# Buttons.net
KiCad netlist of a schematic drawn in EAGLE
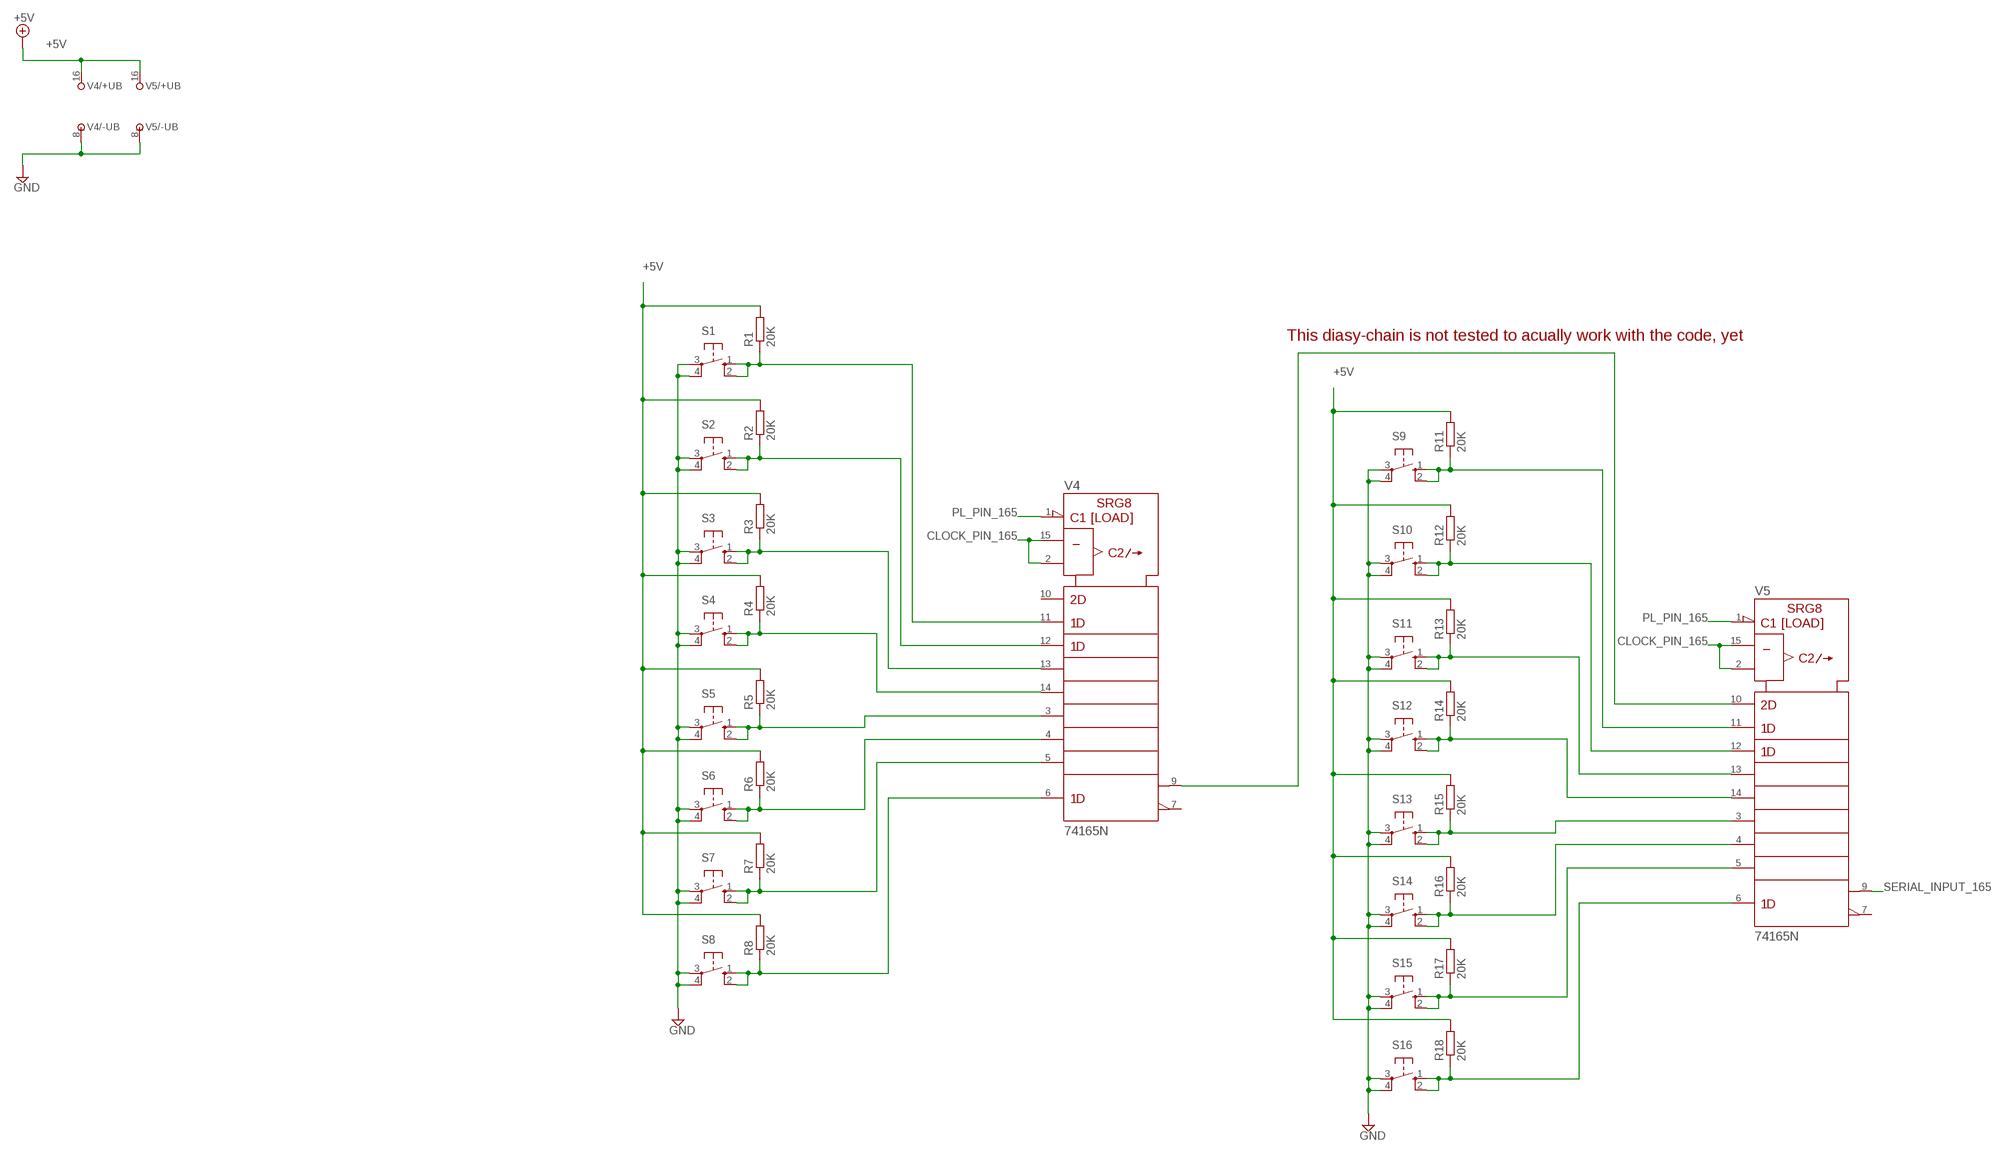
[diagram p0: schematic, sheet 1]

(export (version "E")
  (design (tool "Eeschema 10.0.6"))
  (components
    (comp (ref "R1")
      (value "20K")
      (footprint "eagle-import:0204_7")
      (libsource (lib "eagle-import") (part "R-EU_0204/7"))
    )
    (comp (ref "R2")
      (value "20K")
      (footprint "eagle-import:0204_7")
      (libsource (lib "eagle-import") (part "R-EU_0204/7"))
    )
    (comp (ref "R3")
      (value "20K")
      (footprint "eagle-import:0204_7")
      (libsource (lib "eagle-import") (part "R-EU_0204/7"))
    )
    (comp (ref "R4")
      (value "20K")
      (footprint "eagle-import:0204_7")
      (libsource (lib "eagle-import") (part "R-EU_0204/7"))
    )
    (comp (ref "R5")
      (value "20K")
      (footprint "eagle-import:0204_7")
      (libsource (lib "eagle-import") (part "R-EU_0204/7"))
    )
    (comp (ref "R6")
      (value "20K")
      (footprint "eagle-import:0204_7")
      (libsource (lib "eagle-import") (part "R-EU_0204/7"))
    )
    (comp (ref "R7")
      (value "20K")
      (footprint "eagle-import:0204_7")
      (libsource (lib "eagle-import") (part "R-EU_0204/7"))
    )
    (comp (ref "R8")
      (value "20K")
      (footprint "eagle-import:0204_7")
      (libsource (lib "eagle-import") (part "R-EU_0204/7"))
    )
    (comp (ref "R11")
      (value "20K")
      (footprint "eagle-import:0204_7")
      (libsource (lib "eagle-import") (part "R-EU_0204/7"))
    )
    (comp (ref "R12")
      (value "20K")
      (footprint "eagle-import:0204_7")
      (libsource (lib "eagle-import") (part "R-EU_0204/7"))
    )
    (comp (ref "R13")
      (value "20K")
      (footprint "eagle-import:0204_7")
      (libsource (lib "eagle-import") (part "R-EU_0204/7"))
    )
    (comp (ref "R14")
      (value "20K")
      (footprint "eagle-import:0204_7")
      (libsource (lib "eagle-import") (part "R-EU_0204/7"))
    )
    (comp (ref "R15")
      (value "20K")
      (footprint "eagle-import:0204_7")
      (libsource (lib "eagle-import") (part "R-EU_0204/7"))
    )
    (comp (ref "R16")
      (value "20K")
      (footprint "eagle-import:0204_7")
      (libsource (lib "eagle-import") (part "R-EU_0204/7"))
    )
    (comp (ref "R17")
      (value "20K")
      (footprint "eagle-import:0204_7")
      (libsource (lib "eagle-import") (part "R-EU_0204/7"))
    )
    (comp (ref "R18")
      (value "20K")
      (footprint "eagle-import:0204_7")
      (libsource (lib "eagle-import") (part "R-EU_0204/7"))
    )
    (comp (ref "S1")
      (value "40-XX")
      (footprint "eagle-import:B3F-40XX")
      (fields (field (name "MF") "OMRON COMPONENTS USA") (field (name "MPN") "B3F-4000"))
      (libsource (lib "eagle-import") (part "40-XX"))
    )
    (comp (ref "S2")
      (value "40-XX")
      (footprint "eagle-import:B3F-40XX")
      (fields (field (name "MF") "OMRON COMPONENTS USA") (field (name "MPN") "B3F-4000"))
      (libsource (lib "eagle-import") (part "40-XX"))
    )
    (comp (ref "S3")
      (value "40-XX")
      (footprint "eagle-import:B3F-40XX")
      (fields (field (name "MF") "OMRON COMPONENTS USA") (field (name "MPN") "B3F-4000"))
      (libsource (lib "eagle-import") (part "40-XX"))
    )
    (comp (ref "S4")
      (value "40-XX")
      (footprint "eagle-import:B3F-40XX")
      (fields (field (name "MF") "OMRON COMPONENTS USA") (field (name "MPN") "B3F-4000"))
      (libsource (lib "eagle-import") (part "40-XX"))
    )
    (comp (ref "S5")
      (value "40-XX")
      (footprint "eagle-import:B3F-40XX")
      (fields (field (name "MF") "OMRON COMPONENTS USA") (field (name "MPN") "B3F-4000"))
      (libsource (lib "eagle-import") (part "40-XX"))
    )
    (comp (ref "S6")
      (value "40-XX")
      (footprint "eagle-import:B3F-40XX")
      (fields (field (name "MF") "OMRON COMPONENTS USA") (field (name "MPN") "B3F-4000"))
      (libsource (lib "eagle-import") (part "40-XX"))
    )
    (comp (ref "S7")
      (value "40-XX")
      (footprint "eagle-import:B3F-40XX")
      (fields (field (name "MF") "OMRON COMPONENTS USA") (field (name "MPN") "B3F-4000"))
      (libsource (lib "eagle-import") (part "40-XX"))
    )
    (comp (ref "S8")
      (value "40-XX")
      (footprint "eagle-import:B3F-40XX")
      (fields (field (name "MF") "OMRON COMPONENTS USA") (field (name "MPN") "B3F-4000"))
      (libsource (lib "eagle-import") (part "40-XX"))
    )
    (comp (ref "S9")
      (value "40-XX")
      (footprint "eagle-import:B3F-40XX")
      (fields (field (name "MF") "OMRON COMPONENTS USA") (field (name "MPN") "B3F-4000"))
      (libsource (lib "eagle-import") (part "40-XX"))
    )
    (comp (ref "S10")
      (value "40-XX")
      (footprint "eagle-import:B3F-40XX")
      (fields (field (name "MF") "OMRON COMPONENTS USA") (field (name "MPN") "B3F-4000"))
      (libsource (lib "eagle-import") (part "40-XX"))
    )
    (comp (ref "S11")
      (value "40-XX")
      (footprint "eagle-import:B3F-40XX")
      (fields (field (name "MF") "OMRON COMPONENTS USA") (field (name "MPN") "B3F-4000"))
      (libsource (lib "eagle-import") (part "40-XX"))
    )
    (comp (ref "S12")
      (value "40-XX")
      (footprint "eagle-import:B3F-40XX")
      (fields (field (name "MF") "OMRON COMPONENTS USA") (field (name "MPN") "B3F-4000"))
      (libsource (lib "eagle-import") (part "40-XX"))
    )
    (comp (ref "S13")
      (value "40-XX")
      (footprint "eagle-import:B3F-40XX")
      (fields (field (name "MF") "OMRON COMPONENTS USA") (field (name "MPN") "B3F-4000"))
      (libsource (lib "eagle-import") (part "40-XX"))
    )
    (comp (ref "S14")
      (value "40-XX")
      (footprint "eagle-import:B3F-40XX")
      (fields (field (name "MF") "OMRON COMPONENTS USA") (field (name "MPN") "B3F-4000"))
      (libsource (lib "eagle-import") (part "40-XX"))
    )
    (comp (ref "S15")
      (value "40-XX")
      (footprint "eagle-import:B3F-40XX")
      (fields (field (name "MF") "OMRON COMPONENTS USA") (field (name "MPN") "B3F-4000"))
      (libsource (lib "eagle-import") (part "40-XX"))
    )
    (comp (ref "S16")
      (value "40-XX")
      (footprint "eagle-import:B3F-40XX")
      (fields (field (name "MF") "OMRON COMPONENTS USA") (field (name "MPN") "B3F-4000"))
      (libsource (lib "eagle-import") (part "40-XX"))
    )
    (comp (ref "V4")
      (value "74165N")
      (footprint "eagle-import:DIL16")
      (libsource (lib "eagle-import") (part "74165N"))
    )
    (comp (ref "V5")
      (value "74165N")
      (footprint "eagle-import:DIL16")
      (libsource (lib "eagle-import") (part "74165N"))
    )
  )
  (nets
    (net (code "1") (name "+5V") (class "Default")
      (node (ref "R1") (pin "2") (pinfunction "2_2") (pintype "passive"))
      (node (ref "R11") (pin "2") (pinfunction "2_2") (pintype "passive"))
      (node (ref "R12") (pin "2") (pinfunction "2_2") (pintype "passive"))
      (node (ref "R13") (pin "2") (pinfunction "2_2") (pintype "passive"))
      (node (ref "R14") (pin "2") (pinfunction "2_2") (pintype "passive"))
      (node (ref "R15") (pin "2") (pinfunction "2_2") (pintype "passive"))
      (node (ref "R16") (pin "2") (pinfunction "2_2") (pintype "passive"))
      (node (ref "R17") (pin "2") (pinfunction "2_2") (pintype "passive"))
      (node (ref "R18") (pin "2") (pinfunction "2_2") (pintype "passive"))
      (node (ref "R2") (pin "2") (pinfunction "2_2") (pintype "passive"))
      (node (ref "R3") (pin "2") (pinfunction "2_2") (pintype "passive"))
      (node (ref "R4") (pin "2") (pinfunction "2_2") (pintype "passive"))
      (node (ref "R5") (pin "2") (pinfunction "2_2") (pintype "passive"))
      (node (ref "R6") (pin "2") (pinfunction "2_2") (pintype "passive"))
      (node (ref "R7") (pin "2") (pinfunction "2_2") (pintype "passive"))
      (node (ref "R8") (pin "2") (pinfunction "2_2") (pintype "passive"))
      (node (ref "V4") (pin "16") (pinfunction "+UB_16") (pintype "power_in"))
      (node (ref "V5") (pin "16") (pinfunction "+UB_16") (pintype "power_in"))
    )
    (net (code "2") (name "/CLOCK_PIN_165") (class "Default")
      (node (ref "V4") (pin "15") (pinfunction "CLK_INH_15") (pintype "input"))
      (node (ref "V4") (pin "2") (pinfunction "CLK_2") (pintype "input"))
      (node (ref "V5") (pin "15") (pinfunction "CLK_INH_15") (pintype "input"))
      (node (ref "V5") (pin "2") (pinfunction "CLK_2") (pintype "input"))
    )
    (net (code "3") (name "/PL_PIN_165") (class "Default")
      (node (ref "V4") (pin "1") (pinfunction "SH/~{LD}_1") (pintype "input"))
      (node (ref "V5") (pin "1") (pinfunction "SH/~{LD}_1") (pintype "input"))
    )
    (net (code "4") (name "/SERIAL_INPUT_165") (class "Default")
      (node (ref "V5") (pin "9") (pinfunction "QH_9") (pintype "output"))
    )
    (net (code "5") (name "GND") (class "Default")
      (node (ref "S1") (pin "3") (pinfunction "P_3") (pintype "passive"))
      (node (ref "S1") (pin "4") (pinfunction "P1_4") (pintype "passive"))
      (node (ref "S10") (pin "3") (pinfunction "P_3") (pintype "passive"))
      (node (ref "S10") (pin "4") (pinfunction "P1_4") (pintype "passive"))
      (node (ref "S11") (pin "3") (pinfunction "P_3") (pintype "passive"))
      (node (ref "S11") (pin "4") (pinfunction "P1_4") (pintype "passive"))
      (node (ref "S12") (pin "3") (pinfunction "P_3") (pintype "passive"))
      (node (ref "S12") (pin "4") (pinfunction "P1_4") (pintype "passive"))
      (node (ref "S13") (pin "3") (pinfunction "P_3") (pintype "passive"))
      (node (ref "S13") (pin "4") (pinfunction "P1_4") (pintype "passive"))
      (node (ref "S14") (pin "3") (pinfunction "P_3") (pintype "passive"))
      (node (ref "S14") (pin "4") (pinfunction "P1_4") (pintype "passive"))
      (node (ref "S15") (pin "3") (pinfunction "P_3") (pintype "passive"))
      (node (ref "S15") (pin "4") (pinfunction "P1_4") (pintype "passive"))
      (node (ref "S16") (pin "3") (pinfunction "P_3") (pintype "passive"))
      (node (ref "S16") (pin "4") (pinfunction "P1_4") (pintype "passive"))
      (node (ref "S2") (pin "3") (pinfunction "P_3") (pintype "passive"))
      (node (ref "S2") (pin "4") (pinfunction "P1_4") (pintype "passive"))
      (node (ref "S3") (pin "3") (pinfunction "P_3") (pintype "passive"))
      (node (ref "S3") (pin "4") (pinfunction "P1_4") (pintype "passive"))
      (node (ref "S4") (pin "3") (pinfunction "P_3") (pintype "passive"))
      (node (ref "S4") (pin "4") (pinfunction "P1_4") (pintype "passive"))
      (node (ref "S5") (pin "3") (pinfunction "P_3") (pintype "passive"))
      (node (ref "S5") (pin "4") (pinfunction "P1_4") (pintype "passive"))
      (node (ref "S6") (pin "3") (pinfunction "P_3") (pintype "passive"))
      (node (ref "S6") (pin "4") (pinfunction "P1_4") (pintype "passive"))
      (node (ref "S7") (pin "3") (pinfunction "P_3") (pintype "passive"))
      (node (ref "S7") (pin "4") (pinfunction "P1_4") (pintype "passive"))
      (node (ref "S8") (pin "3") (pinfunction "P_3") (pintype "passive"))
      (node (ref "S8") (pin "4") (pinfunction "P1_4") (pintype "passive"))
      (node (ref "S9") (pin "3") (pinfunction "P_3") (pintype "passive"))
      (node (ref "S9") (pin "4") (pinfunction "P1_4") (pintype "passive"))
      (node (ref "V4") (pin "8") (pinfunction "-UB_8") (pintype "power_in"))
      (node (ref "V5") (pin "8") (pinfunction "-UB_8") (pintype "power_in"))
    )
    (net (code "6") (name "Net-(S1-S)") (class "Default")
      (node (ref "R1") (pin "1") (pinfunction "1_1") (pintype "passive"))
      (node (ref "S1") (pin "1") (pinfunction "S_1") (pintype "passive"))
      (node (ref "S1") (pin "2") (pinfunction "S1_2") (pintype "passive"))
      (node (ref "V4") (pin "11") (pinfunction "A_11") (pintype "input"))
    )
    (net (code "7") (name "Net-(S2-S)") (class "Default")
      (node (ref "R2") (pin "1") (pinfunction "1_1") (pintype "passive"))
      (node (ref "S2") (pin "1") (pinfunction "S_1") (pintype "passive"))
      (node (ref "S2") (pin "2") (pinfunction "S1_2") (pintype "passive"))
      (node (ref "V4") (pin "12") (pinfunction "B_12") (pintype "input"))
    )
    (net (code "8") (name "Net-(S3-S)") (class "Default")
      (node (ref "R3") (pin "1") (pinfunction "1_1") (pintype "passive"))
      (node (ref "S3") (pin "1") (pinfunction "S_1") (pintype "passive"))
      (node (ref "S3") (pin "2") (pinfunction "S1_2") (pintype "passive"))
      (node (ref "V4") (pin "13") (pinfunction "C_13") (pintype "input"))
    )
    (net (code "9") (name "Net-(S4-S)") (class "Default")
      (node (ref "R4") (pin "1") (pinfunction "1_1") (pintype "passive"))
      (node (ref "S4") (pin "1") (pinfunction "S_1") (pintype "passive"))
      (node (ref "S4") (pin "2") (pinfunction "S1_2") (pintype "passive"))
      (node (ref "V4") (pin "14") (pinfunction "D_14") (pintype "input"))
    )
    (net (code "10") (name "Net-(S5-S)") (class "Default")
      (node (ref "R5") (pin "1") (pinfunction "1_1") (pintype "passive"))
      (node (ref "S5") (pin "1") (pinfunction "S_1") (pintype "passive"))
      (node (ref "S5") (pin "2") (pinfunction "S1_2") (pintype "passive"))
      (node (ref "V4") (pin "3") (pinfunction "E_3") (pintype "input"))
    )
    (net (code "11") (name "Net-(S6-S)") (class "Default")
      (node (ref "R6") (pin "1") (pinfunction "1_1") (pintype "passive"))
      (node (ref "S6") (pin "1") (pinfunction "S_1") (pintype "passive"))
      (node (ref "S6") (pin "2") (pinfunction "S1_2") (pintype "passive"))
      (node (ref "V4") (pin "4") (pinfunction "F_4") (pintype "input"))
    )
    (net (code "12") (name "Net-(S7-S)") (class "Default")
      (node (ref "R7") (pin "1") (pinfunction "1_1") (pintype "passive"))
      (node (ref "S7") (pin "1") (pinfunction "S_1") (pintype "passive"))
      (node (ref "S7") (pin "2") (pinfunction "S1_2") (pintype "passive"))
      (node (ref "V4") (pin "5") (pinfunction "G_5") (pintype "input"))
    )
    (net (code "13") (name "Net-(S8-S)") (class "Default")
      (node (ref "R8") (pin "1") (pinfunction "1_1") (pintype "passive"))
      (node (ref "S8") (pin "1") (pinfunction "S_1") (pintype "passive"))
      (node (ref "S8") (pin "2") (pinfunction "S1_2") (pintype "passive"))
      (node (ref "V4") (pin "6") (pinfunction "H_6") (pintype "input"))
    )
    (net (code "14") (name "Net-(S9-S)") (class "Default")
      (node (ref "R11") (pin "1") (pinfunction "1_1") (pintype "passive"))
      (node (ref "S9") (pin "1") (pinfunction "S_1") (pintype "passive"))
      (node (ref "S9") (pin "2") (pinfunction "S1_2") (pintype "passive"))
      (node (ref "V5") (pin "11") (pinfunction "A_11") (pintype "input"))
    )
    (net (code "15") (name "Net-(S10-S)") (class "Default")
      (node (ref "R12") (pin "1") (pinfunction "1_1") (pintype "passive"))
      (node (ref "S10") (pin "1") (pinfunction "S_1") (pintype "passive"))
      (node (ref "S10") (pin "2") (pinfunction "S1_2") (pintype "passive"))
      (node (ref "V5") (pin "12") (pinfunction "B_12") (pintype "input"))
    )
    (net (code "16") (name "Net-(S11-S)") (class "Default")
      (node (ref "R13") (pin "1") (pinfunction "1_1") (pintype "passive"))
      (node (ref "S11") (pin "1") (pinfunction "S_1") (pintype "passive"))
      (node (ref "S11") (pin "2") (pinfunction "S1_2") (pintype "passive"))
      (node (ref "V5") (pin "13") (pinfunction "C_13") (pintype "input"))
    )
    (net (code "17") (name "Net-(S12-S)") (class "Default")
      (node (ref "R14") (pin "1") (pinfunction "1_1") (pintype "passive"))
      (node (ref "S12") (pin "1") (pinfunction "S_1") (pintype "passive"))
      (node (ref "S12") (pin "2") (pinfunction "S1_2") (pintype "passive"))
      (node (ref "V5") (pin "14") (pinfunction "D_14") (pintype "input"))
    )
    (net (code "18") (name "Net-(S13-S)") (class "Default")
      (node (ref "R15") (pin "1") (pinfunction "1_1") (pintype "passive"))
      (node (ref "S13") (pin "1") (pinfunction "S_1") (pintype "passive"))
      (node (ref "S13") (pin "2") (pinfunction "S1_2") (pintype "passive"))
      (node (ref "V5") (pin "3") (pinfunction "E_3") (pintype "input"))
    )
    (net (code "19") (name "Net-(S14-S)") (class "Default")
      (node (ref "R16") (pin "1") (pinfunction "1_1") (pintype "passive"))
      (node (ref "S14") (pin "1") (pinfunction "S_1") (pintype "passive"))
      (node (ref "S14") (pin "2") (pinfunction "S1_2") (pintype "passive"))
      (node (ref "V5") (pin "4") (pinfunction "F_4") (pintype "input"))
    )
    (net (code "20") (name "Net-(S15-S)") (class "Default")
      (node (ref "R17") (pin "1") (pinfunction "1_1") (pintype "passive"))
      (node (ref "S15") (pin "1") (pinfunction "S_1") (pintype "passive"))
      (node (ref "S15") (pin "2") (pinfunction "S1_2") (pintype "passive"))
      (node (ref "V5") (pin "5") (pinfunction "G_5") (pintype "input"))
    )
    (net (code "21") (name "Net-(S16-S)") (class "Default")
      (node (ref "R18") (pin "1") (pinfunction "1_1") (pintype "passive"))
      (node (ref "S16") (pin "1") (pinfunction "S_1") (pintype "passive"))
      (node (ref "S16") (pin "2") (pinfunction "S1_2") (pintype "passive"))
      (node (ref "V5") (pin "6") (pinfunction "H_6") (pintype "input"))
    )
    (net (code "22") (name "Net-(V4C-QH)") (class "Default")
      (node (ref "V4") (pin "9") (pinfunction "QH_9") (pintype "output"))
      (node (ref "V5") (pin "10") (pinfunction "SER_10") (pintype "input"))
    )
    (net (code "23") (name "unconnected-(V4C-SER-Pad10)") (class "Default")
      (node (ref "V4") (pin "10") (pinfunction "SER_10") (pintype "input"))
    )
    (net (code "24") (name "unconnected-(V4C-~{QH}-Pad7)") (class "Default")
      (node (ref "V4") (pin "7") (pinfunction "~{QH}_7") (pintype "output"))
    )
    (net (code "25") (name "unconnected-(V5C-~{QH}-Pad7)") (class "Default")
      (node (ref "V5") (pin "7") (pinfunction "~{QH}_7") (pintype "output"))
    )
  )
)
